# PR_Schema.net
KiCad netlist of a schematic drawn in Altium Designer
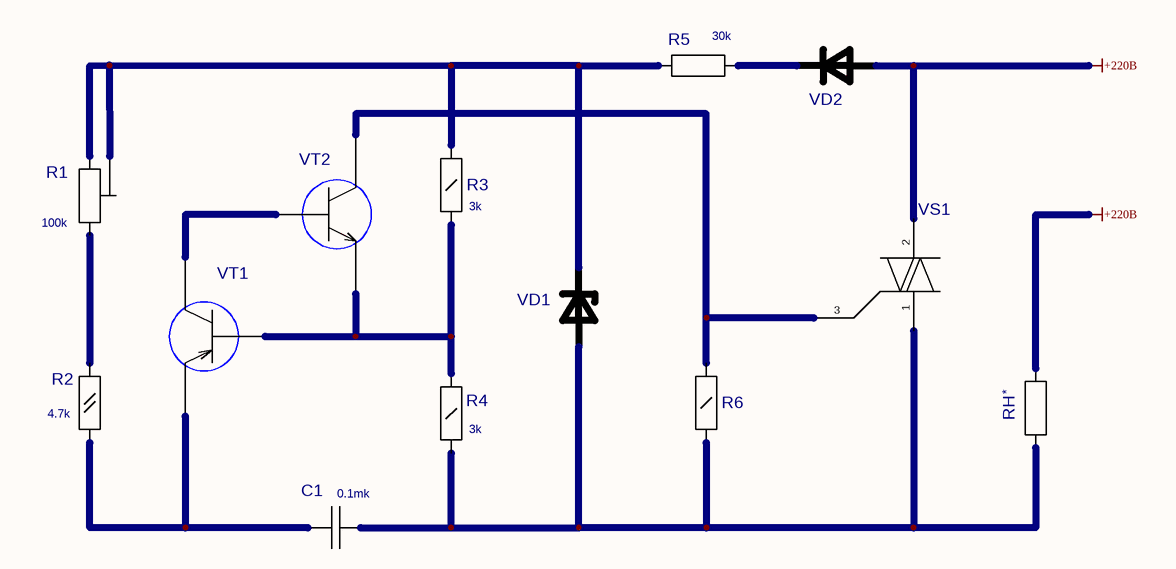
[diagram p0: PR_Schema.SchDoc]

(export (version "E")
  (design (tool "Eeschema 10.0.6"))
  (components
    (comp (ref "C1")
      (value "0.1mk")
      (footprint "1812_DIP")
      (description "К10-17БИМП-NP0-0,01МКФ-1812")
      (libsource (lib "*") (part "К10-17БИМП-NP0-0,01МКФ-1812"))
    )
    (comp (ref "R1")
      (value "100k")
      (footprint "3006P")
      (description "3006W")
      (libsource (lib "*") (part "3006W"))
    )
    (comp (ref "R2")
      (value "4.7k")
      (footprint "C2-33H-0.125W")
      (description "C2-33H-0.125W_OLD_UGO")
      (fields (field (name "AUTOR") "pcbdesigner.ru"))
      (libsource (lib "*") (part "C2-33H-0.125W_OLD_UGO"))
    )
    (comp (ref "R3")
      (value "3k")
      (footprint "C2-33H-0.25W")
      (description "C2-33H-0.25W_OLD_UGO")
      (fields (field (name "AUTOR") "pcbdesigner.ru"))
      (libsource (lib "*") (part "C2-33H-0.25W_OLD_UGO"))
    )
    (comp (ref "R4")
      (value "3k")
      (footprint "C2-33H-0.25W")
      (description "C2-33H-0.25W_OLD_UGO")
      (fields (field (name "AUTOR") "pcbdesigner.ru"))
      (libsource (lib "*") (part "C2-33H-0.25W_OLD_UGO"))
    )
    (comp (ref "R5")
      (value "30k")
      (footprint "C5-16MB-5BT")
      (description "C5-16MB-5BT")
      (libsource (lib "*") (part "C5-16MB-5BT"))
    )
    (comp (ref "R6")
      (value "C2-33H-0.25W_OLD_UGO")
      (footprint "C2-33H-0.25W")
      (fields (field (name "AUTOR") "pcbdesigner.ru"))
      (libsource (lib "*") (part "C2-33H-0.25W_OLD_UGO"))
    )
    (comp (ref "RH")
      (value "C5-16MB-5BT")
      (footprint "C5-16MB-5BT")
      (fields (field (name "ALTIUM_VALUE") "*"))
      (libsource (lib "*") (part "C5-16MB-5BT"))
    )
    (comp (ref "VD1") (value "BZX55-C30V") (footprint "DO-35") (libsource (lib "*") (part "BZX55-C30V")))
    (comp (ref "VD2") (value "КД105Б") (footprint "КД105") (libsource (lib "*") (part "КД105Б")))
    (comp (ref "VS1") (value "TC106") (footprint "KT-27") (libsource (lib "*") (part "TC106")))
    (comp (ref "VT1") (value "КТ361А") (footprint "KT13") (libsource (lib "*") (part "КТ361А")))
    (comp (ref "VT2") (value "КТ315А") (footprint "KT13") (libsource (lib "*") (part "КТ315А")))
  )
  (nets
    (net (code "1") (name "+220B") (class "Default")
      (node (ref "RH") (pin "2") (pinfunction "2_2") (pintype "passive"))
      (node (ref "VD2") (pin "A") (pinfunction "A_A") (pintype "passive"))
      (node (ref "VS1") (pin "2") (pinfunction "E2_2") (pintype "passive"))
    )
    (net (code "2") (name "Net-(R1-Pad1)") (class "Default")
      (node (ref "R1") (pin "1") (pinfunction "1_1") (pintype "passive"))
      (node (ref "R2") (pin "1") (pinfunction "1_1") (pintype "passive"))
    )
    (net (code "3") (name "Net-(R1-Pad2)") (class "Default")
      (node (ref "R1") (pin "2") (pinfunction "2_2") (pintype "passive"))
      (node (ref "R1") (pin "3") (pinfunction "3_3") (pintype "passive"))
      (node (ref "R3") (pin "2") (pinfunction "2_2") (pintype "passive"))
      (node (ref "R5") (pin "1") (pinfunction "1_1") (pintype "passive"))
      (node (ref "VD1") (pin "K") (pinfunction "K_K") (pintype "passive"))
    )
    (net (code "4") (name "Net-(R5-Pad2)") (class "Default")
      (node (ref "R5") (pin "2") (pinfunction "2_2") (pintype "passive"))
      (node (ref "VD2") (pin "K") (pinfunction "K_K") (pintype "passive"))
    )
    (net (code "5") (name "Net-(VS1-E1)") (class "Default")
      (node (ref "C1") (pin "2") (pinfunction "2_2") (pintype "passive"))
      (node (ref "R4") (pin "1") (pinfunction "1_1") (pintype "passive"))
      (node (ref "R6") (pin "1") (pinfunction "1_1") (pintype "passive"))
      (node (ref "RH") (pin "1") (pinfunction "1_1") (pintype "passive"))
      (node (ref "VD1") (pin "A") (pinfunction "A_A") (pintype "passive"))
      (node (ref "VS1") (pin "1") (pinfunction "E1_1") (pintype "passive"))
    )
    (net (code "6") (name "Net-(VS1-Ue)") (class "Default")
      (node (ref "R6") (pin "2") (pinfunction "2_2") (pintype "passive"))
      (node (ref "VS1") (pin "3") (pinfunction "Ue_3") (pintype "passive"))
      (node (ref "VT2") (pin "3") (pinfunction "K_3") (pintype "passive"))
    )
    (net (code "7") (name "Net-(VT1-B)") (class "Default")
      (node (ref "R3") (pin "1") (pinfunction "1_1") (pintype "passive"))
      (node (ref "R4") (pin "2") (pinfunction "2_2") (pintype "passive"))
      (node (ref "VT1") (pin "2") (pinfunction "B_2") (pintype "passive"))
      (node (ref "VT2") (pin "1") (pinfunction "E_1") (pintype "passive"))
    )
    (net (code "8") (name "Net-(VT1-E)") (class "Default")
      (node (ref "C1") (pin "1") (pinfunction "1_1") (pintype "passive"))
      (node (ref "R2") (pin "2") (pinfunction "2_2") (pintype "passive"))
      (node (ref "VT1") (pin "1") (pinfunction "E_1") (pintype "passive"))
    )
    (net (code "9") (name "Net-(VT1-K)") (class "Default")
      (node (ref "VT1") (pin "3") (pinfunction "K_3") (pintype "passive"))
      (node (ref "VT2") (pin "2") (pinfunction "B_2") (pintype "passive"))
    )
  )
)
